# VCAMixer.net
KiCad netlist of a schematic drawn in EAGLE
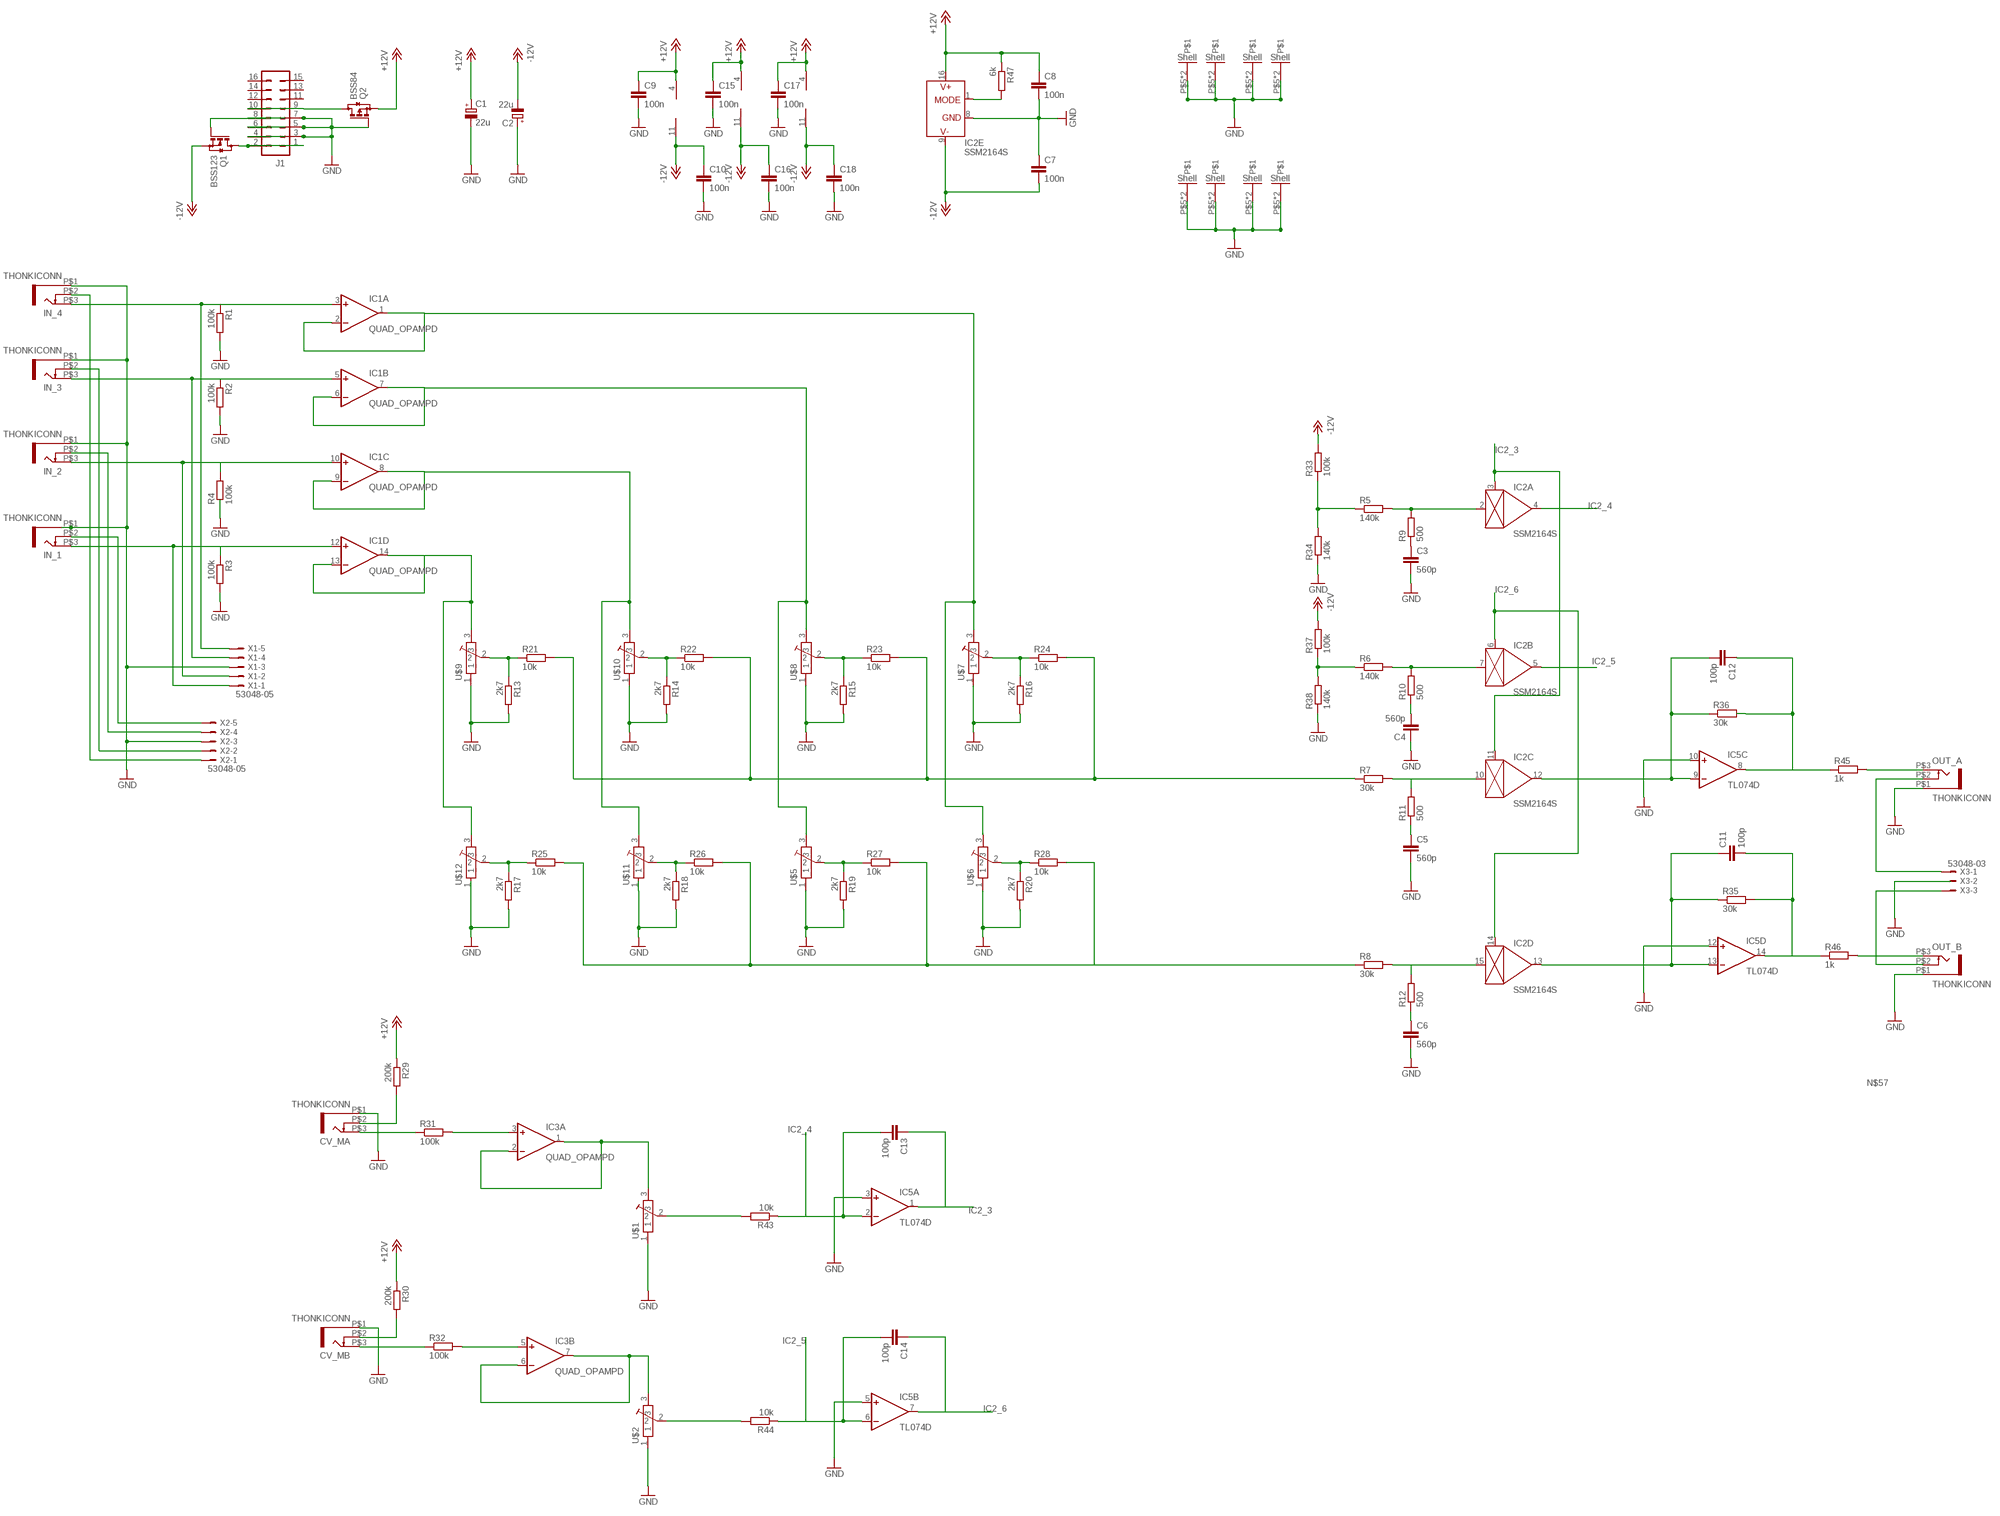
[diagram p0: schematic, sheet 1]

(export (version "E")
  (design (tool "Eeschema 10.0.6"))
  (components
    (comp (ref "C1")
      (value "22u")
      (footprint "eagle-import:153CLV-0505")
      (libsource (lib "eagle-import") (part "CPOL-EU153CLV-0505"))
    )
    (comp (ref "C2")
      (value "22u")
      (footprint "eagle-import:153CLV-0505")
      (libsource (lib "eagle-import") (part "CPOL-EU153CLV-0505"))
    )
    (comp (ref "C3")
      (value "560p")
      (footprint "eagle-import:C0603K")
      (libsource (lib "eagle-import") (part "C-EUC0603K"))
    )
    (comp (ref "C4")
      (value "560p")
      (footprint "eagle-import:C0603K")
      (libsource (lib "eagle-import") (part "C-EUC0603K"))
    )
    (comp (ref "C5")
      (value "560p")
      (footprint "eagle-import:C0603K")
      (libsource (lib "eagle-import") (part "C-EUC0603K"))
    )
    (comp (ref "C6")
      (value "560p")
      (footprint "eagle-import:C0603K")
      (libsource (lib "eagle-import") (part "C-EUC0603K"))
    )
    (comp (ref "C7")
      (value "100n")
      (footprint "eagle-import:C0603K")
      (libsource (lib "eagle-import") (part "C-EUC0603K"))
    )
    (comp (ref "C8")
      (value "100n")
      (footprint "eagle-import:C0603K")
      (libsource (lib "eagle-import") (part "C-EUC0603K"))
    )
    (comp (ref "C9")
      (value "100n")
      (footprint "eagle-import:C0603K")
      (libsource (lib "eagle-import") (part "C-EUC0603K"))
    )
    (comp (ref "C10")
      (value "100n")
      (footprint "eagle-import:C0603K")
      (libsource (lib "eagle-import") (part "C-EUC0603K"))
    )
    (comp (ref "C11")
      (value "100p")
      (footprint "eagle-import:C0603K")
      (libsource (lib "eagle-import") (part "C-EUC0603K"))
    )
    (comp (ref "C12")
      (value "100p")
      (footprint "eagle-import:C0603K")
      (libsource (lib "eagle-import") (part "C-EUC0603K"))
    )
    (comp (ref "C13")
      (value "100p")
      (footprint "eagle-import:C0603K")
      (libsource (lib "eagle-import") (part "C-EUC0603K"))
    )
    (comp (ref "C14")
      (value "100p")
      (footprint "eagle-import:C0603K")
      (libsource (lib "eagle-import") (part "C-EUC0603K"))
    )
    (comp (ref "C15")
      (value "100n")
      (footprint "eagle-import:C0603K")
      (libsource (lib "eagle-import") (part "C-EUC0603K"))
    )
    (comp (ref "C16")
      (value "100n")
      (footprint "eagle-import:C0603K")
      (libsource (lib "eagle-import") (part "C-EUC0603K"))
    )
    (comp (ref "C17")
      (value "100n")
      (footprint "eagle-import:C0603K")
      (libsource (lib "eagle-import") (part "C-EUC0603K"))
    )
    (comp (ref "C18")
      (value "100n")
      (footprint "eagle-import:C0603K")
      (libsource (lib "eagle-import") (part "C-EUC0603K"))
    )
    (comp (ref "CV_MA")
      (value "THONKICONN")
      (footprint "eagle-import:THONKICONN")
      (libsource (lib "eagle-import") (part "THONKICONN"))
    )
    (comp (ref "CV_MB")
      (value "THONKICONN")
      (footprint "eagle-import:THONKICONN")
      (libsource (lib "eagle-import") (part "THONKICONN"))
    )
    (comp (ref "IC1")
      (value "QUAD_OPAMPD")
      (footprint "eagle-import:SO14")
      (libsource (lib "eagle-import") (part "QUAD_OPAMPD"))
    )
    (comp (ref "IC2")
      (value "SSM2164S")
      (footprint "eagle-import:SOIC16N")
      (libsource (lib "eagle-import") (part "SSM2164S"))
    )
    (comp (ref "IC3")
      (value "QUAD_OPAMPD")
      (footprint "eagle-import:SO14")
      (libsource (lib "eagle-import") (part "QUAD_OPAMPD"))
    )
    (comp (ref "IC5")
      (value "TL074D")
      (footprint "eagle-import:SO14")
      (libsource (lib "eagle-import") (part "TL074D"))
    )
    (comp (ref "IN_1")
      (value "THONKICONN")
      (footprint "eagle-import:THONKICONN")
      (libsource (lib "eagle-import") (part "THONKICONN"))
    )
    (comp (ref "IN_2")
      (value "THONKICONN")
      (footprint "eagle-import:THONKICONN")
      (libsource (lib "eagle-import") (part "THONKICONN"))
    )
    (comp (ref "IN_3")
      (value "THONKICONN")
      (footprint "eagle-import:THONKICONN")
      (libsource (lib "eagle-import") (part "THONKICONN"))
    )
    (comp (ref "IN_4")
      (value "THONKICONN")
      (footprint "eagle-import:THONKICONN")
      (libsource (lib "eagle-import") (part "THONKICONN"))
    )
    (comp (ref "J1")
      (value "M08X2")
      (footprint "eagle-import:2X8")
      (libsource (lib "eagle-import") (part "M08X2"))
    )
    (comp (ref "OUT_A")
      (value "THONKICONN")
      (footprint "eagle-import:THONKICONN")
      (libsource (lib "eagle-import") (part "THONKICONN"))
    )
    (comp (ref "OUT_B")
      (value "THONKICONN")
      (footprint "eagle-import:THONKICONN")
      (libsource (lib "eagle-import") (part "THONKICONN"))
    )
    (comp (ref "Q1")
      (value "BSS123")
      (footprint "eagle-import:SOT23")
      (libsource (lib "eagle-import") (part "BSS123"))
    )
    (comp (ref "Q2")
      (value "BSS84")
      (footprint "eagle-import:SOT23")
      (libsource (lib "eagle-import") (part "BSS84"))
    )
    (comp (ref "R1")
      (value "100k")
      (footprint "eagle-import:0603")
      (libsource (lib "eagle-import") (part "R-EU_0603"))
    )
    (comp (ref "R2")
      (value "100k")
      (footprint "eagle-import:0603")
      (libsource (lib "eagle-import") (part "R-EU_0603"))
    )
    (comp (ref "R3")
      (value "100k")
      (footprint "eagle-import:0603")
      (libsource (lib "eagle-import") (part "R-EU_0603"))
    )
    (comp (ref "R4")
      (value "100k")
      (footprint "eagle-import:0603")
      (libsource (lib "eagle-import") (part "R-EU_0603"))
    )
    (comp (ref "R5")
      (value "140k")
      (footprint "eagle-import:0603")
      (libsource (lib "eagle-import") (part "R-EU_0603"))
    )
    (comp (ref "R6")
      (value "140k")
      (footprint "eagle-import:0603")
      (libsource (lib "eagle-import") (part "R-EU_0603"))
    )
    (comp (ref "R7")
      (value "30k")
      (footprint "eagle-import:0603")
      (libsource (lib "eagle-import") (part "R-EU_0603"))
    )
    (comp (ref "R8")
      (value "30k")
      (footprint "eagle-import:0603")
      (libsource (lib "eagle-import") (part "R-EU_0603"))
    )
    (comp (ref "R9")
      (value "500")
      (footprint "eagle-import:0603")
      (libsource (lib "eagle-import") (part "R-EU_0603"))
    )
    (comp (ref "R10")
      (value "500")
      (footprint "eagle-import:0603")
      (libsource (lib "eagle-import") (part "R-EU_0603"))
    )
    (comp (ref "R11")
      (value "500")
      (footprint "eagle-import:0603")
      (libsource (lib "eagle-import") (part "R-EU_0603"))
    )
    (comp (ref "R12")
      (value "500")
      (footprint "eagle-import:0603")
      (libsource (lib "eagle-import") (part "R-EU_0603"))
    )
    (comp (ref "R13")
      (value "2k7")
      (footprint "eagle-import:0603")
      (libsource (lib "eagle-import") (part "R-EU_0603"))
    )
    (comp (ref "R14")
      (value "2k7")
      (footprint "eagle-import:0603")
      (libsource (lib "eagle-import") (part "R-EU_0603"))
    )
    (comp (ref "R15")
      (value "2k7")
      (footprint "eagle-import:0603")
      (libsource (lib "eagle-import") (part "R-EU_0603"))
    )
    (comp (ref "R16")
      (value "2k7")
      (footprint "eagle-import:0603")
      (libsource (lib "eagle-import") (part "R-EU_0603"))
    )
    (comp (ref "R17")
      (value "2k7")
      (footprint "eagle-import:0603")
      (libsource (lib "eagle-import") (part "R-EU_0603"))
    )
    (comp (ref "R18")
      (value "2k7")
      (footprint "eagle-import:0603")
      (libsource (lib "eagle-import") (part "R-EU_0603"))
    )
    (comp (ref "R19")
      (value "2k7")
      (footprint "eagle-import:0603")
      (libsource (lib "eagle-import") (part "R-EU_0603"))
    )
    (comp (ref "R20")
      (value "2k7")
      (footprint "eagle-import:0603")
      (libsource (lib "eagle-import") (part "R-EU_0603"))
    )
    (comp (ref "R21")
      (value "10k")
      (footprint "eagle-import:0603")
      (libsource (lib "eagle-import") (part "R-EU_0603"))
    )
    (comp (ref "R22")
      (value "10k")
      (footprint "eagle-import:0603")
      (libsource (lib "eagle-import") (part "R-EU_0603"))
    )
    (comp (ref "R23")
      (value "10k")
      (footprint "eagle-import:0603")
      (libsource (lib "eagle-import") (part "R-EU_0603"))
    )
    (comp (ref "R24")
      (value "10k")
      (footprint "eagle-import:0603")
      (libsource (lib "eagle-import") (part "R-EU_0603"))
    )
    (comp (ref "R25")
      (value "10k")
      (footprint "eagle-import:0603")
      (libsource (lib "eagle-import") (part "R-EU_0603"))
    )
    (comp (ref "R26")
      (value "10k")
      (footprint "eagle-import:0603")
      (libsource (lib "eagle-import") (part "R-EU_0603"))
    )
    (comp (ref "R27")
      (value "10k")
      (footprint "eagle-import:0603")
      (libsource (lib "eagle-import") (part "R-EU_0603"))
    )
    (comp (ref "R28")
      (value "10k")
      (footprint "eagle-import:0603")
      (libsource (lib "eagle-import") (part "R-EU_0603"))
    )
    (comp (ref "R29")
      (value "200k")
      (footprint "eagle-import:0603")
      (libsource (lib "eagle-import") (part "R-EU_0603"))
    )
    (comp (ref "R30")
      (value "200k")
      (footprint "eagle-import:0603")
      (libsource (lib "eagle-import") (part "R-EU_0603"))
    )
    (comp (ref "R31")
      (value "100k")
      (footprint "eagle-import:0603")
      (libsource (lib "eagle-import") (part "R-EU_0603"))
    )
    (comp (ref "R32")
      (value "100k")
      (footprint "eagle-import:0603")
      (libsource (lib "eagle-import") (part "R-EU_0603"))
    )
    (comp (ref "R33")
      (value "100k")
      (footprint "eagle-import:0603")
      (libsource (lib "eagle-import") (part "R-EU_0603"))
    )
    (comp (ref "R34")
      (value "140k")
      (footprint "eagle-import:0603")
      (libsource (lib "eagle-import") (part "R-EU_0603"))
    )
    (comp (ref "R35")
      (value "30k")
      (footprint "eagle-import:0603")
      (libsource (lib "eagle-import") (part "R-EU_0603"))
    )
    (comp (ref "R36")
      (value "30k")
      (footprint "eagle-import:0603")
      (libsource (lib "eagle-import") (part "R-EU_0603"))
    )
    (comp (ref "R37")
      (value "100k")
      (footprint "eagle-import:0603")
      (libsource (lib "eagle-import") (part "R-EU_0603"))
    )
    (comp (ref "R38")
      (value "140k")
      (footprint "eagle-import:0603")
      (libsource (lib "eagle-import") (part "R-EU_0603"))
    )
    (comp (ref "R43")
      (value "10k")
      (footprint "eagle-import:0603")
      (libsource (lib "eagle-import") (part "R-EU_0603"))
    )
    (comp (ref "R44")
      (value "10k")
      (footprint "eagle-import:0603")
      (libsource (lib "eagle-import") (part "R-EU_0603"))
    )
    (comp (ref "R45")
      (value "1k")
      (footprint "eagle-import:0603")
      (libsource (lib "eagle-import") (part "R-EU_0603"))
    )
    (comp (ref "R46")
      (value "1k")
      (footprint "eagle-import:0603")
      (libsource (lib "eagle-import") (part "R-EU_0603"))
    )
    (comp (ref "R47")
      (value "6k")
      (footprint "eagle-import:0603")
      (libsource (lib "eagle-import") (part "R-EU_0603"))
    )
    (comp (ref "U$1")
      (value "POT-ALPS-RK09L1140")
      (footprint "eagle-import:POT-ALPS-RK09L1140")
      (libsource (lib "eagle-import") (part "POT-ALPS-RK09L1140"))
    )
    (comp (ref "U$2")
      (value "POT-ALPS-RK09L1140")
      (footprint "eagle-import:POT-ALPS-RK09L1140")
      (libsource (lib "eagle-import") (part "POT-ALPS-RK09L1140"))
    )
    (comp (ref "U$5")
      (value "POT-ALPS-RK09L1140")
      (footprint "eagle-import:POT-ALPS-RK09L1140")
      (libsource (lib "eagle-import") (part "POT-ALPS-RK09L1140"))
    )
    (comp (ref "U$6")
      (value "POT-ALPS-RK09L1140")
      (footprint "eagle-import:POT-ALPS-RK09L1140")
      (libsource (lib "eagle-import") (part "POT-ALPS-RK09L1140"))
    )
    (comp (ref "U$7")
      (value "POT-ALPS-RK09L1140")
      (footprint "eagle-import:POT-ALPS-RK09L1140")
      (libsource (lib "eagle-import") (part "POT-ALPS-RK09L1140"))
    )
    (comp (ref "U$8")
      (value "POT-ALPS-RK09L1140")
      (footprint "eagle-import:POT-ALPS-RK09L1140")
      (libsource (lib "eagle-import") (part "POT-ALPS-RK09L1140"))
    )
    (comp (ref "U$9")
      (value "POT-ALPS-RK09L1140")
      (footprint "eagle-import:POT-ALPS-RK09L1140")
      (libsource (lib "eagle-import") (part "POT-ALPS-RK09L1140"))
    )
    (comp (ref "U$10")
      (value "POT-ALPS-RK09L1140")
      (footprint "eagle-import:POT-ALPS-RK09L1140")
      (libsource (lib "eagle-import") (part "POT-ALPS-RK09L1140"))
    )
    (comp (ref "U$11")
      (value "POT-ALPS-RK09L1140")
      (footprint "eagle-import:POT-ALPS-RK09L1140")
      (libsource (lib "eagle-import") (part "POT-ALPS-RK09L1140"))
    )
    (comp (ref "U$12")
      (value "POT-ALPS-RK09L1140")
      (footprint "eagle-import:POT-ALPS-RK09L1140")
      (libsource (lib "eagle-import") (part "POT-ALPS-RK09L1140"))
    )
    (comp (ref "X1")
      (value "53048-05")
      (footprint "eagle-import:53048-05")
      (fields (field (name "MF") "MOLEX") (field (name "MPN") "53048-0510"))
      (libsource (lib "eagle-import") (part "53?-05048"))
    )
    (comp (ref "X2")
      (value "53048-05")
      (footprint "eagle-import:53048-05")
      (fields (field (name "MF") "MOLEX") (field (name "MPN") "53048-0510"))
      (libsource (lib "eagle-import") (part "53?-05048"))
    )
    (comp (ref "X3")
      (value "53048-03")
      (footprint "eagle-import:53048-03")
      (fields (field (name "MF") "WALDOM/MOLEX") (field (name "MPN") "53048-0310"))
      (libsource (lib "eagle-import") (part "53?-03048"))
    )
  )
  (nets
    (net (code "1") (name "+12V") (class "Default")
      (node (ref "C1") (pin "+") (pinfunction "+_+") (pintype "passive"))
      (node (ref "C15") (pin "1") (pinfunction "1_1") (pintype "passive"))
      (node (ref "C17") (pin "1") (pinfunction "1_1") (pintype "passive"))
      (node (ref "C8") (pin "1") (pinfunction "1_1") (pintype "passive"))
      (node (ref "C9") (pin "1") (pinfunction "1_1") (pintype "passive"))
      (node (ref "IC1") (pin "4") (pinfunction "V+_4") (pintype "power_in"))
      (node (ref "IC2") (pin "16") (pinfunction "V+_16") (pintype "power_in"))
      (node (ref "IC3") (pin "4") (pinfunction "V+_4") (pintype "power_in"))
      (node (ref "IC5") (pin "4") (pinfunction "V+_4") (pintype "power_in"))
      (node (ref "Q2") (pin "2") (pinfunction "S_2") (pintype "passive"))
      (node (ref "R29") (pin "1") (pinfunction "1_1") (pintype "passive"))
      (node (ref "R30") (pin "1") (pinfunction "1_1") (pintype "passive"))
      (node (ref "R47") (pin "1") (pinfunction "1_1") (pintype "passive"))
    )
    (net (code "2") (name "-12V") (class "Default")
      (node (ref "C10") (pin "1") (pinfunction "1_1") (pintype "passive"))
      (node (ref "C16") (pin "1") (pinfunction "1_1") (pintype "passive"))
      (node (ref "C18") (pin "1") (pinfunction "1_1") (pintype "passive"))
      (node (ref "C2") (pin "-") (pinfunction "-_-") (pintype "passive"))
      (node (ref "C7") (pin "2") (pinfunction "2_2") (pintype "passive"))
      (node (ref "IC1") (pin "11") (pinfunction "V-_11") (pintype "power_in"))
      (node (ref "IC2") (pin "9") (pinfunction "V-_9") (pintype "power_in"))
      (node (ref "IC3") (pin "11") (pinfunction "V-_11") (pintype "power_in"))
      (node (ref "IC5") (pin "11") (pinfunction "V-_11") (pintype "power_in"))
      (node (ref "Q1") (pin "2") (pinfunction "S_2") (pintype "passive"))
      (node (ref "R33") (pin "2") (pinfunction "2_2") (pintype "passive"))
      (node (ref "R37") (pin "2") (pinfunction "2_2") (pintype "passive"))
    )
    (net (code "3") (name "/IC2_3") (class "Default")
      (node (ref "C13") (pin "1") (pinfunction "1_1") (pintype "passive"))
      (node (ref "IC2") (pin "11") (pinfunction "CTRL_11") (pintype "input"))
      (node (ref "IC2") (pin "3") (pinfunction "CTRL_3") (pintype "input"))
      (node (ref "IC5") (pin "1") (pinfunction "OUT_1") (pintype "output"))
    )
    (net (code "4") (name "/IC2_4") (class "Default")
      (node (ref "C13") (pin "2") (pinfunction "2_2") (pintype "passive"))
      (node (ref "IC2") (pin "4") (pinfunction "OUT_4") (pintype "output"))
      (node (ref "IC5") (pin "2") (pinfunction "-IN_2") (pintype "input"))
      (node (ref "R43") (pin "1") (pinfunction "1_1") (pintype "passive"))
    )
    (net (code "5") (name "/IC2_5") (class "Default")
      (node (ref "C14") (pin "2") (pinfunction "2_2") (pintype "passive"))
      (node (ref "IC2") (pin "5") (pinfunction "OUT_5") (pintype "output"))
      (node (ref "IC5") (pin "6") (pinfunction "-IN_6") (pintype "input"))
      (node (ref "R44") (pin "1") (pinfunction "1_1") (pintype "passive"))
    )
    (net (code "6") (name "/IC2_6") (class "Default")
      (node (ref "C14") (pin "1") (pinfunction "1_1") (pintype "passive"))
      (node (ref "IC2") (pin "14") (pinfunction "CTRL_14") (pintype "input"))
      (node (ref "IC2") (pin "6") (pinfunction "CTRL_6") (pintype "input"))
      (node (ref "IC5") (pin "7") (pinfunction "OUT_7") (pintype "output"))
    )
    (net (code "7") (name "/N$57") (class "Default")
      (node (ref "OUT_B") (pin "P$2") (pinfunction "4_P$2") (pintype "passive"))
      (node (ref "X3") (pin "3") (pinfunction "S_3") (pintype "passive"))
    )
    (net (code "8") (name "GND") (class "Default")
      (node (ref "C1") (pin "-") (pinfunction "-_-") (pintype "passive"))
      (node (ref "C10") (pin "2") (pinfunction "2_2") (pintype "passive"))
      (node (ref "C15") (pin "2") (pinfunction "2_2") (pintype "passive"))
      (node (ref "C16") (pin "2") (pinfunction "2_2") (pintype "passive"))
      (node (ref "C17") (pin "2") (pinfunction "2_2") (pintype "passive"))
      (node (ref "C18") (pin "2") (pinfunction "2_2") (pintype "passive"))
      (node (ref "C2") (pin "+") (pinfunction "+_+") (pintype "passive"))
      (node (ref "C3") (pin "2") (pinfunction "2_2") (pintype "passive"))
      (node (ref "C4") (pin "1") (pinfunction "1_1") (pintype "passive"))
      (node (ref "C5") (pin "2") (pinfunction "2_2") (pintype "passive"))
      (node (ref "C6") (pin "2") (pinfunction "2_2") (pintype "passive"))
      (node (ref "C7") (pin "1") (pinfunction "1_1") (pintype "passive"))
      (node (ref "C8") (pin "2") (pinfunction "2_2") (pintype "passive"))
      (node (ref "C9") (pin "2") (pinfunction "2_2") (pintype "passive"))
      (node (ref "CV_MA") (pin "P$1") (pinfunction "5_P$1") (pintype "passive"))
      (node (ref "CV_MB") (pin "P$1") (pinfunction "5_P$1") (pintype "passive"))
      (node (ref "IC2") (pin "8") (pinfunction "GND_8") (pintype "power_in"))
      (node (ref "IC5") (pin "10") (pinfunction "+IN_10") (pintype "input"))
      (node (ref "IC5") (pin "12") (pinfunction "+IN_12") (pintype "input"))
      (node (ref "IC5") (pin "3") (pinfunction "+IN_3") (pintype "input"))
      (node (ref "IC5") (pin "5") (pinfunction "+IN_5") (pintype "input"))
      (node (ref "IN_1") (pin "P$1") (pinfunction "5_P$1") (pintype "passive"))
      (node (ref "IN_2") (pin "P$1") (pinfunction "5_P$1") (pintype "passive"))
      (node (ref "IN_3") (pin "P$1") (pinfunction "5_P$1") (pintype "passive"))
      (node (ref "IN_4") (pin "P$1") (pinfunction "5_P$1") (pintype "passive"))
      (node (ref "J1") (pin "3") (pinfunction "3_3") (pintype "passive"))
      (node (ref "J1") (pin "5") (pinfunction "5_5") (pintype "passive"))
      (node (ref "J1") (pin "7") (pinfunction "7_7") (pintype "passive"))
      (node (ref "OUT_A") (pin "P$1") (pinfunction "5_P$1") (pintype "passive"))
      (node (ref "OUT_B") (pin "P$1") (pinfunction "5_P$1") (pintype "passive"))
      (node (ref "Q2") (pin "1") (pinfunction "G_1") (pintype "passive"))
      (node (ref "R1") (pin "2") (pinfunction "2_2") (pintype "passive"))
      (node (ref "R13") (pin "2") (pinfunction "2_2") (pintype "passive"))
      (node (ref "R14") (pin "2") (pinfunction "2_2") (pintype "passive"))
      (node (ref "R15") (pin "2") (pinfunction "2_2") (pintype "passive"))
      (node (ref "R16") (pin "2") (pinfunction "2_2") (pintype "passive"))
      (node (ref "R17") (pin "2") (pinfunction "2_2") (pintype "passive"))
      (node (ref "R18") (pin "2") (pinfunction "2_2") (pintype "passive"))
      (node (ref "R19") (pin "2") (pinfunction "2_2") (pintype "passive"))
      (node (ref "R2") (pin "2") (pinfunction "2_2") (pintype "passive"))
      (node (ref "R20") (pin "2") (pinfunction "2_2") (pintype "passive"))
      (node (ref "R3") (pin "2") (pinfunction "2_2") (pintype "passive"))
      (node (ref "R34") (pin "1") (pinfunction "1_1") (pintype "passive"))
      (node (ref "R38") (pin "1") (pinfunction "1_1") (pintype "passive"))
      (node (ref "U$1") (pin "1") (pinfunction "1_1") (pintype "bidirectional"))
      (node (ref "U$10") (pin "1") (pinfunction "1_1") (pintype "bidirectional"))
      (node (ref "U$10") (pin "P$5") (pinfunction "P$1_P$5") (pintype "bidirectional"))
      (node (ref "U$10") (pin "P$6") (pinfunction "P$1_P$6") (pintype "bidirectional"))
      (node (ref "U$11") (pin "1") (pinfunction "1_1") (pintype "bidirectional"))
      (node (ref "U$11") (pin "P$5") (pinfunction "P$1_P$5") (pintype "bidirectional"))
      (node (ref "U$11") (pin "P$6") (pinfunction "P$1_P$6") (pintype "bidirectional"))
      (node (ref "U$12") (pin "1") (pinfunction "1_1") (pintype "bidirectional"))
      (node (ref "U$12") (pin "P$5") (pinfunction "P$1_P$5") (pintype "bidirectional"))
      (node (ref "U$12") (pin "P$6") (pinfunction "P$1_P$6") (pintype "bidirectional"))
      (node (ref "U$2") (pin "1") (pinfunction "1_1") (pintype "bidirectional"))
      (node (ref "U$5") (pin "1") (pinfunction "1_1") (pintype "bidirectional"))
      (node (ref "U$5") (pin "P$5") (pinfunction "P$1_P$5") (pintype "bidirectional"))
      (node (ref "U$5") (pin "P$6") (pinfunction "P$1_P$6") (pintype "bidirectional"))
      (node (ref "U$6") (pin "1") (pinfunction "1_1") (pintype "bidirectional"))
      (node (ref "U$6") (pin "P$5") (pinfunction "P$1_P$5") (pintype "bidirectional"))
      (node (ref "U$6") (pin "P$6") (pinfunction "P$1_P$6") (pintype "bidirectional"))
      (node (ref "U$7") (pin "1") (pinfunction "1_1") (pintype "bidirectional"))
      (node (ref "U$7") (pin "P$5") (pinfunction "P$1_P$5") (pintype "bidirectional"))
      (node (ref "U$7") (pin "P$6") (pinfunction "P$1_P$6") (pintype "bidirectional"))
      (node (ref "U$8") (pin "1") (pinfunction "1_1") (pintype "bidirectional"))
      (node (ref "U$8") (pin "P$5") (pinfunction "P$1_P$5") (pintype "bidirectional"))
      (node (ref "U$8") (pin "P$6") (pinfunction "P$1_P$6") (pintype "bidirectional"))
      (node (ref "U$9") (pin "1") (pinfunction "1_1") (pintype "bidirectional"))
      (node (ref "U$9") (pin "P$5") (pinfunction "P$1_P$5") (pintype "bidirectional"))
      (node (ref "U$9") (pin "P$6") (pinfunction "P$1_P$6") (pintype "bidirectional"))
      (node (ref "X1") (pin "3") (pinfunction "S_3") (pintype "passive"))
      (node (ref "X2") (pin "3") (pinfunction "S_3") (pintype "passive"))
    )
    (net (code "9") (name "Net-(C3-Pad1)") (class "Default")
      (node (ref "C3") (pin "1") (pinfunction "1_1") (pintype "passive"))
      (node (ref "R9") (pin "1") (pinfunction "1_1") (pintype "passive"))
    )
    (net (code "10") (name "Net-(C4-Pad2)") (class "Default")
      (node (ref "C4") (pin "2") (pinfunction "2_2") (pintype "passive"))
      (node (ref "R10") (pin "1") (pinfunction "1_1") (pintype "passive"))
    )
    (net (code "11") (name "Net-(C5-Pad1)") (class "Default")
      (node (ref "C5") (pin "1") (pinfunction "1_1") (pintype "passive"))
      (node (ref "R11") (pin "1") (pinfunction "1_1") (pintype "passive"))
    )
    (net (code "12") (name "Net-(C6-Pad1)") (class "Default")
      (node (ref "C6") (pin "1") (pinfunction "1_1") (pintype "passive"))
      (node (ref "R12") (pin "1") (pinfunction "1_1") (pintype "passive"))
    )
    (net (code "13") (name "Net-(CV_MA-3)") (class "Default")
      (node (ref "CV_MA") (pin "P$3") (pinfunction "3_P$3") (pintype "passive"))
      (node (ref "R31") (pin "1") (pinfunction "1_1") (pintype "passive"))
    )
    (net (code "14") (name "Net-(CV_MA-4)") (class "Default")
      (node (ref "CV_MA") (pin "P$2") (pinfunction "4_P$2") (pintype "passive"))
      (node (ref "R29") (pin "2") (pinfunction "2_2") (pintype "passive"))
    )
    (net (code "15") (name "Net-(CV_MB-3)") (class "Default")
      (node (ref "CV_MB") (pin "P$3") (pinfunction "3_P$3") (pintype "passive"))
      (node (ref "R32") (pin "1") (pinfunction "1_1") (pintype "passive"))
    )
    (net (code "16") (name "Net-(CV_MB-4)") (class "Default")
      (node (ref "CV_MB") (pin "P$2") (pinfunction "4_P$2") (pintype "passive"))
      (node (ref "R30") (pin "2") (pinfunction "2_2") (pintype "passive"))
    )
    (net (code "17") (name "Net-(IC1A-+IN)") (class "Default")
      (node (ref "IC1") (pin "3") (pinfunction "+IN_3") (pintype "input"))
      (node (ref "IN_4") (pin "P$3") (pinfunction "3_P$3") (pintype "passive"))
      (node (ref "R1") (pin "1") (pinfunction "1_1") (pintype "passive"))
      (node (ref "X1") (pin "5") (pinfunction "S_5") (pintype "passive"))
    )
    (net (code "18") (name "Net-(IC1A--IN)") (class "Default")
      (node (ref "IC1") (pin "1") (pinfunction "OUT_1") (pintype "output"))
      (node (ref "IC1") (pin "2") (pinfunction "-IN_2") (pintype "input"))
      (node (ref "U$6") (pin "3") (pinfunction "3_3") (pintype "bidirectional"))
      (node (ref "U$7") (pin "3") (pinfunction "3_3") (pintype "bidirectional"))
    )
    (net (code "19") (name "Net-(IC1B-+IN)") (class "Default")
      (node (ref "IC1") (pin "5") (pinfunction "+IN_5") (pintype "input"))
      (node (ref "IN_3") (pin "P$3") (pinfunction "3_P$3") (pintype "passive"))
      (node (ref "R2") (pin "1") (pinfunction "1_1") (pintype "passive"))
      (node (ref "X1") (pin "4") (pinfunction "S_4") (pintype "passive"))
    )
    (net (code "20") (name "Net-(IC1B--IN)") (class "Default")
      (node (ref "IC1") (pin "6") (pinfunction "-IN_6") (pintype "input"))
      (node (ref "IC1") (pin "7") (pinfunction "OUT_7") (pintype "output"))
      (node (ref "U$5") (pin "3") (pinfunction "3_3") (pintype "bidirectional"))
      (node (ref "U$8") (pin "3") (pinfunction "3_3") (pintype "bidirectional"))
    )
    (net (code "21") (name "Net-(IC1C-+IN)") (class "Default")
      (node (ref "IC1") (pin "10") (pinfunction "+IN_10") (pintype "input"))
      (node (ref "IN_2") (pin "P$3") (pinfunction "3_P$3") (pintype "passive"))
      (node (ref "R4") (pin "2") (pinfunction "2_2") (pintype "passive"))
      (node (ref "X1") (pin "2") (pinfunction "S_2") (pintype "passive"))
    )
    (net (code "22") (name "Net-(IC1C--IN)") (class "Default")
      (node (ref "IC1") (pin "8") (pinfunction "OUT_8") (pintype "output"))
      (node (ref "IC1") (pin "9") (pinfunction "-IN_9") (pintype "input"))
      (node (ref "U$10") (pin "3") (pinfunction "3_3") (pintype "bidirectional"))
      (node (ref "U$11") (pin "3") (pinfunction "3_3") (pintype "bidirectional"))
    )
    (net (code "23") (name "Net-(IC1D-+IN)") (class "Default")
      (node (ref "IC1") (pin "12") (pinfunction "+IN_12") (pintype "input"))
      (node (ref "IN_1") (pin "P$3") (pinfunction "3_P$3") (pintype "passive"))
      (node (ref "R3") (pin "1") (pinfunction "1_1") (pintype "passive"))
      (node (ref "X1") (pin "1") (pinfunction "S_1") (pintype "passive"))
    )
    (net (code "24") (name "Net-(IC1D--IN)") (class "Default")
      (node (ref "IC1") (pin "13") (pinfunction "-IN_13") (pintype "input"))
      (node (ref "IC1") (pin "14") (pinfunction "OUT_14") (pintype "output"))
      (node (ref "U$12") (pin "3") (pinfunction "3_3") (pintype "bidirectional"))
      (node (ref "U$9") (pin "3") (pinfunction "3_3") (pintype "bidirectional"))
    )
    (net (code "25") (name "Net-(IC2A-IN)") (class "Default")
      (node (ref "IC2") (pin "2") (pinfunction "IN_2") (pintype "input"))
      (node (ref "R5") (pin "2") (pinfunction "2_2") (pintype "passive"))
      (node (ref "R9") (pin "2") (pinfunction "2_2") (pintype "passive"))
    )
    (net (code "26") (name "Net-(IC2B-IN)") (class "Default")
      (node (ref "IC2") (pin "7") (pinfunction "IN_7") (pintype "input"))
      (node (ref "R10") (pin "2") (pinfunction "2_2") (pintype "passive"))
      (node (ref "R6") (pin "2") (pinfunction "2_2") (pintype "passive"))
    )
    (net (code "27") (name "Net-(IC2C-IN)") (class "Default")
      (node (ref "IC2") (pin "10") (pinfunction "IN_10") (pintype "input"))
      (node (ref "R11") (pin "2") (pinfunction "2_2") (pintype "passive"))
      (node (ref "R7") (pin "2") (pinfunction "2_2") (pintype "passive"))
    )
    (net (code "28") (name "Net-(IC2C-OUT)") (class "Default")
      (node (ref "C12") (pin "2") (pinfunction "2_2") (pintype "passive"))
      (node (ref "IC2") (pin "12") (pinfunction "OUT_12") (pintype "output"))
      (node (ref "IC5") (pin "9") (pinfunction "-IN_9") (pintype "input"))
      (node (ref "R36") (pin "1") (pinfunction "1_1") (pintype "passive"))
    )
    (net (code "29") (name "Net-(IC2D-IN)") (class "Default")
      (node (ref "IC2") (pin "15") (pinfunction "IN_15") (pintype "input"))
      (node (ref "R12") (pin "2") (pinfunction "2_2") (pintype "passive"))
      (node (ref "R8") (pin "2") (pinfunction "2_2") (pintype "passive"))
    )
    (net (code "30") (name "Net-(IC2D-OUT)") (class "Default")
      (node (ref "C11") (pin "1") (pinfunction "1_1") (pintype "passive"))
      (node (ref "IC2") (pin "13") (pinfunction "OUT_13") (pintype "output"))
      (node (ref "IC5") (pin "13") (pinfunction "-IN_13") (pintype "input"))
      (node (ref "R35") (pin "1") (pinfunction "1_1") (pintype "passive"))
    )
    (net (code "31") (name "Net-(IC2E-MODE)") (class "Default")
      (node (ref "IC2") (pin "1") (pinfunction "MODE_1") (pintype "input"))
      (node (ref "R47") (pin "2") (pinfunction "2_2") (pintype "passive"))
    )
    (net (code "32") (name "Net-(IC3A-+IN)") (class "Default")
      (node (ref "IC3") (pin "3") (pinfunction "+IN_3") (pintype "input"))
      (node (ref "R31") (pin "2") (pinfunction "2_2") (pintype "passive"))
    )
    (net (code "33") (name "Net-(IC3A--IN)") (class "Default")
      (node (ref "IC3") (pin "1") (pinfunction "OUT_1") (pintype "output"))
      (node (ref "IC3") (pin "2") (pinfunction "-IN_2") (pintype "input"))
      (node (ref "U$1") (pin "3") (pinfunction "3_3") (pintype "bidirectional"))
    )
    (net (code "34") (name "Net-(IC3B-+IN)") (class "Default")
      (node (ref "IC3") (pin "5") (pinfunction "+IN_5") (pintype "input"))
      (node (ref "R32") (pin "2") (pinfunction "2_2") (pintype "passive"))
    )
    (net (code "35") (name "Net-(IC3B--IN)") (class "Default")
      (node (ref "IC3") (pin "6") (pinfunction "-IN_6") (pintype "input"))
      (node (ref "IC3") (pin "7") (pinfunction "OUT_7") (pintype "output"))
      (node (ref "U$2") (pin "3") (pinfunction "3_3") (pintype "bidirectional"))
    )
    (net (code "36") (name "Net-(IC5C-OUT)") (class "Default")
      (node (ref "C12") (pin "1") (pinfunction "1_1") (pintype "passive"))
      (node (ref "IC5") (pin "8") (pinfunction "OUT_8") (pintype "output"))
      (node (ref "R36") (pin "2") (pinfunction "2_2") (pintype "passive"))
      (node (ref "R45") (pin "1") (pinfunction "1_1") (pintype "passive"))
    )
    (net (code "37") (name "Net-(IC5D-OUT)") (class "Default")
      (node (ref "C11") (pin "2") (pinfunction "2_2") (pintype "passive"))
      (node (ref "IC5") (pin "14") (pinfunction "OUT_14") (pintype "output"))
      (node (ref "R35") (pin "2") (pinfunction "2_2") (pintype "passive"))
      (node (ref "R46") (pin "1") (pinfunction "1_1") (pintype "passive"))
    )
    (net (code "38") (name "Net-(IN_1-4)") (class "Default")
      (node (ref "IN_1") (pin "P$2") (pinfunction "4_P$2") (pintype "passive"))
      (node (ref "X2") (pin "5") (pinfunction "S_5") (pintype "passive"))
    )
    (net (code "39") (name "Net-(IN_2-4)") (class "Default")
      (node (ref "IN_2") (pin "P$2") (pinfunction "4_P$2") (pintype "passive"))
      (node (ref "X2") (pin "4") (pinfunction "S_4") (pintype "passive"))
    )
    (net (code "40") (name "Net-(IN_3-4)") (class "Default")
      (node (ref "IN_3") (pin "P$2") (pinfunction "4_P$2") (pintype "passive"))
      (node (ref "X2") (pin "2") (pinfunction "S_2") (pintype "passive"))
    )
    (net (code "41") (name "Net-(IN_4-4)") (class "Default")
      (node (ref "IN_4") (pin "P$2") (pinfunction "4_P$2") (pintype "passive"))
      (node (ref "X2") (pin "1") (pinfunction "S_1") (pintype "passive"))
    )
    (net (code "42") (name "Net-(OUT_A-3)") (class "Default")
      (node (ref "OUT_A") (pin "P$3") (pinfunction "3_P$3") (pintype "passive"))
      (node (ref "R45") (pin "2") (pinfunction "2_2") (pintype "passive"))
    )
    (net (code "43") (name "Net-(OUT_A-4)") (class "Default")
      (node (ref "OUT_A") (pin "P$2") (pinfunction "4_P$2") (pintype "passive"))
      (node (ref "X3") (pin "1") (pinfunction "S_1") (pintype "passive"))
    )
    (net (code "44") (name "Net-(OUT_B-3)") (class "Default")
      (node (ref "OUT_B") (pin "P$3") (pinfunction "3_P$3") (pintype "passive"))
      (node (ref "R46") (pin "2") (pinfunction "2_2") (pintype "passive"))
    )
    (net (code "45") (name "Net-(Q1-D)") (class "Default")
      (node (ref "J1") (pin "1") (pinfunction "1_1") (pintype "passive"))
      (node (ref "J1") (pin "2") (pinfunction "2_2") (pintype "passive"))
      (node (ref "Q1") (pin "3") (pinfunction "D_3") (pintype "passive"))
    )
    (net (code "46") (name "Net-(Q1-G)") (class "Default")
      (node (ref "J1") (pin "8") (pinfunction "8_8") (pintype "passive"))
      (node (ref "Q1") (pin "1") (pinfunction "G_1") (pintype "passive"))
    )
    (net (code "47") (name "Net-(Q2-D)") (class "Default")
      (node (ref "J1") (pin "10") (pinfunction "10_10") (pintype "passive"))
      (node (ref "J1") (pin "9") (pinfunction "9_9") (pintype "passive"))
      (node (ref "Q2") (pin "3") (pinfunction "D_3") (pintype "passive"))
    )
    (net (code "48") (name "Net-(R13-Pad1)") (class "Default")
      (node (ref "R13") (pin "1") (pinfunction "1_1") (pintype "passive"))
      (node (ref "R21") (pin "1") (pinfunction "1_1") (pintype "passive"))
      (node (ref "U$9") (pin "2") (pinfunction "2_2") (pintype "bidirectional"))
    )
    (net (code "49") (name "Net-(R14-Pad1)") (class "Default")
      (node (ref "R14") (pin "1") (pinfunction "1_1") (pintype "passive"))
      (node (ref "R22") (pin "1") (pinfunction "1_1") (pintype "passive"))
      (node (ref "U$10") (pin "2") (pinfunction "2_2") (pintype "bidirectional"))
    )
    (net (code "50") (name "Net-(R15-Pad1)") (class "Default")
      (node (ref "R15") (pin "1") (pinfunction "1_1") (pintype "passive"))
      (node (ref "R23") (pin "1") (pinfunction "1_1") (pintype "passive"))
      (node (ref "U$8") (pin "2") (pinfunction "2_2") (pintype "bidirectional"))
    )
    (net (code "51") (name "Net-(R16-Pad1)") (class "Default")
      (node (ref "R16") (pin "1") (pinfunction "1_1") (pintype "passive"))
      (node (ref "R24") (pin "1") (pinfunction "1_1") (pintype "passive"))
      (node (ref "U$7") (pin "2") (pinfunction "2_2") (pintype "bidirectional"))
    )
    (net (code "52") (name "Net-(R17-Pad1)") (class "Default")
      (node (ref "R17") (pin "1") (pinfunction "1_1") (pintype "passive"))
      (node (ref "R25") (pin "1") (pinfunction "1_1") (pintype "passive"))
      (node (ref "U$12") (pin "2") (pinfunction "2_2") (pintype "bidirectional"))
    )
    (net (code "53") (name "Net-(R18-Pad1)") (class "Default")
      (node (ref "R18") (pin "1") (pinfunction "1_1") (pintype "passive"))
      (node (ref "R26") (pin "1") (pinfunction "1_1") (pintype "passive"))
      (node (ref "U$11") (pin "2") (pinfunction "2_2") (pintype "bidirectional"))
    )
    (net (code "54") (name "Net-(R19-Pad1)") (class "Default")
      (node (ref "R19") (pin "1") (pinfunction "1_1") (pintype "passive"))
      (node (ref "R27") (pin "1") (pinfunction "1_1") (pintype "passive"))
      (node (ref "U$5") (pin "2") (pinfunction "2_2") (pintype "bidirectional"))
    )
    (net (code "55") (name "Net-(R20-Pad1)") (class "Default")
      (node (ref "R20") (pin "1") (pinfunction "1_1") (pintype "passive"))
      (node (ref "R28") (pin "1") (pinfunction "1_1") (pintype "passive"))
      (node (ref "U$6") (pin "2") (pinfunction "2_2") (pintype "bidirectional"))
    )
    (net (code "56") (name "Net-(R21-Pad2)") (class "Default")
      (node (ref "R21") (pin "2") (pinfunction "2_2") (pintype "passive"))
      (node (ref "R22") (pin "2") (pinfunction "2_2") (pintype "passive"))
      (node (ref "R23") (pin "2") (pinfunction "2_2") (pintype "passive"))
      (node (ref "R24") (pin "2") (pinfunction "2_2") (pintype "passive"))
      (node (ref "R7") (pin "1") (pinfunction "1_1") (pintype "passive"))
    )
    (net (code "57") (name "Net-(R25-Pad2)") (class "Default")
      (node (ref "R25") (pin "2") (pinfunction "2_2") (pintype "passive"))
      (node (ref "R26") (pin "2") (pinfunction "2_2") (pintype "passive"))
      (node (ref "R27") (pin "2") (pinfunction "2_2") (pintype "passive"))
      (node (ref "R28") (pin "2") (pinfunction "2_2") (pintype "passive"))
      (node (ref "R8") (pin "1") (pinfunction "1_1") (pintype "passive"))
    )
    (net (code "58") (name "Net-(R33-Pad1)") (class "Default")
      (node (ref "R33") (pin "1") (pinfunction "1_1") (pintype "passive"))
      (node (ref "R34") (pin "2") (pinfunction "2_2") (pintype "passive"))
      (node (ref "R5") (pin "1") (pinfunction "1_1") (pintype "passive"))
    )
    (net (code "59") (name "Net-(R37-Pad1)") (class "Default")
      (node (ref "R37") (pin "1") (pinfunction "1_1") (pintype "passive"))
      (node (ref "R38") (pin "2") (pinfunction "2_2") (pintype "passive"))
      (node (ref "R6") (pin "1") (pinfunction "1_1") (pintype "passive"))
    )
    (net (code "60") (name "Net-(R43-Pad2)") (class "Default")
      (node (ref "R43") (pin "2") (pinfunction "2_2") (pintype "passive"))
      (node (ref "U$1") (pin "2") (pinfunction "2_2") (pintype "bidirectional"))
    )
    (net (code "61") (name "Net-(R44-Pad2)") (class "Default")
      (node (ref "R44") (pin "2") (pinfunction "2_2") (pintype "passive"))
      (node (ref "U$2") (pin "2") (pinfunction "2_2") (pintype "bidirectional"))
    )
    (net (code "62") (name "unconnected-(J1-Pad4)") (class "Default")
      (node (ref "J1") (pin "4") (pinfunction "4_4") (pintype "passive"))
    )
    (net (code "63") (name "unconnected-(J1-Pad6)") (class "Default")
      (node (ref "J1") (pin "6") (pinfunction "6_6") (pintype "passive"))
    )
    (net (code "64") (name "unconnected-(J1-Pad11)") (class "Default")
      (node (ref "J1") (pin "11") (pinfunction "11_11") (pintype "passive"))
    )
    (net (code "65") (name "unconnected-(J1-Pad12)") (class "Default")
      (node (ref "J1") (pin "12") (pinfunction "12_12") (pintype "passive"))
    )
    (net (code "66") (name "unconnected-(J1-Pad13)") (class "Default")
      (node (ref "J1") (pin "13") (pinfunction "13_13") (pintype "passive"))
    )
    (net (code "67") (name "unconnected-(J1-Pad14)") (class "Default")
      (node (ref "J1") (pin "14") (pinfunction "14_14") (pintype "passive"))
    )
    (net (code "68") (name "unconnected-(J1-Pad15)") (class "Default")
      (node (ref "J1") (pin "15") (pinfunction "15_15") (pintype "passive"))
    )
    (net (code "69") (name "unconnected-(J1-Pad16)") (class "Default")
      (node (ref "J1") (pin "16") (pinfunction "16_16") (pintype "passive"))
    )
    (net (code "70") (name "unconnected-(R4-Pad1)") (class "Default")
      (node (ref "R4") (pin "1") (pinfunction "1_1") (pintype "passive"))
    )
    (net (code "71") (name "unconnected-(X3B-S-Pad2)") (class "Default")
      (node (ref "X3") (pin "2") (pinfunction "S_2") (pintype "passive"))
    )
  )
)
